# POWER.net
KiCad netlist of a schematic drawn in Altium Designer
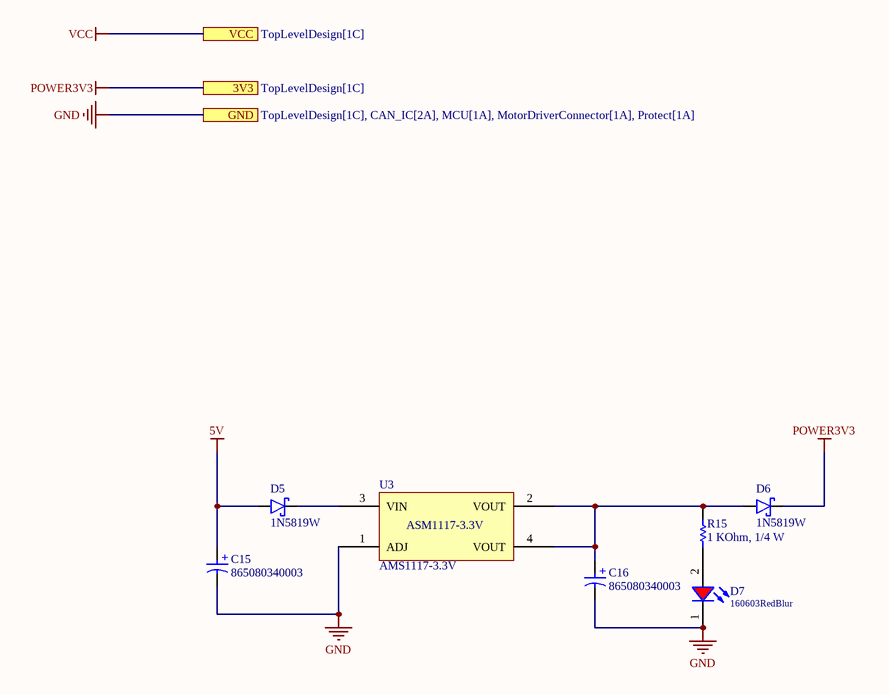
[diagram p0: POWER.SchDoc]

(export (version "E")
  (design (tool "Eeschema 10.0.6"))
  (components
    (comp (ref "C15")
      (value "865080340003")
      (footprint "WCAP-ASLI_D4H5.5")
      (description "V-Chip, D4 x H5.5mm, 22uF, 16V")
      (fields (field (name "MANUFACTURER") "Wurth Elektronik"))
      (libsource (lib "Tin Tran") (part "0710101508650801570160U20"))
    )
    (comp (ref "C16")
      (value "865080340003")
      (footprint "WCAP-ASLI_D4H5.5")
      (description "V-Chip, D4 x H5.5mm, 22uF, 16V")
      (fields (field (name "MANUFACTURER") "Wurth Elektronik"))
      (libsource (lib "Tin Tran") (part "0710101508650801570160U20"))
    )
    (comp (ref "D5") (value "1N5819W") (footprint "1N5819W") (libsource (lib "Tin Tran") (part "1N5819W")))
    (comp (ref "D6") (value "1N5819W") (footprint "1N5819W") (libsource (lib "Tin Tran") (part "1N5819W")))
    (comp (ref "D7")
      (value "160603RedBlur")
      (footprint "WL-SMCW_0603_H=0.7mm")
      (description "WL-SMCW SMT Mono-color Chip LED Blur, size 0603, Red, 2V, 140deg")
      (libsource (lib "Tin Tran") (part "160603RedClear"))
    )
    (comp (ref "R15")
      (value "1 KOhm, 1/4 W")
      (footprint "resistor_0603")
      (description "RES, size 0603, 1 KOhm, 1/4 W")
      (fields (field (name "Comment") "0006031021"))
      (libsource (lib "Tin Tran") (part "00060371541"))
    )
    (comp (ref "U3")
      (value "AMS1117-3.3V")
      (footprint "AMS1117-3.3V SOT223")
      (description "AMS1117-3.3V, OUT 3.3V 1A.")
      (fields (field (name "MANUFACTURER") "AMS") (field (name "SOURCE") "AMS_family.SchLib"))
      (libsource (lib "Tin Tran") (part "AMS1117-3.3V"))
    )
  )
  (nets
    (net (code "1") (name "5V") (class "Default")
      (node (ref "C15") (pin "1") (pinfunction "P_1") (pintype "passive"))
      (node (ref "D5") (pin "A") (pinfunction "A_A") (pintype "passive"))
    )
    (net (code "2") (name "GND") (class "Default")
      (node (ref "C15") (pin "2") (pinfunction "N_2") (pintype "passive"))
      (node (ref "C16") (pin "2") (pinfunction "N_2") (pintype "passive"))
      (node (ref "D7") (pin "1") (pinfunction "K_1") (pintype "passive"))
      (node (ref "U3") (pin "1") (pinfunction "ADJ_1") (pintype "power_in"))
    )
    (net (code "3") (name "Net-(C16-P)") (class "Default")
      (node (ref "C16") (pin "1") (pinfunction "P_1") (pintype "passive"))
      (node (ref "D6") (pin "A") (pinfunction "A_A") (pintype "passive"))
      (node (ref "R15") (pin "2") (pinfunction "2_2") (pintype "passive"))
      (node (ref "U3") (pin "2") (pinfunction "VOUT_2") (pintype "passive"))
      (node (ref "U3") (pin "4") (pinfunction "VOUT_4") (pintype "power_in"))
    )
    (net (code "4") (name "Net-(D7-A)") (class "Default")
      (node (ref "D7") (pin "2") (pinfunction "A_2") (pintype "passive"))
      (node (ref "R15") (pin "1") (pinfunction "1_1") (pintype "passive"))
    )
    (net (code "5") (name "Net-(U3-VIN)") (class "Default")
      (node (ref "D5") (pin "K") (pinfunction "K_K") (pintype "passive"))
      (node (ref "U3") (pin "3") (pinfunction "VIN_3") (pintype "passive"))
    )
    (net (code "6") (name "POWER3V3") (class "Default")
      (node (ref "D6") (pin "K") (pinfunction "K_K") (pintype "passive"))
    )
  )
)
